# BEESP_CODE_io.net
KiCad netlist of a schematic drawn in Altium Designer
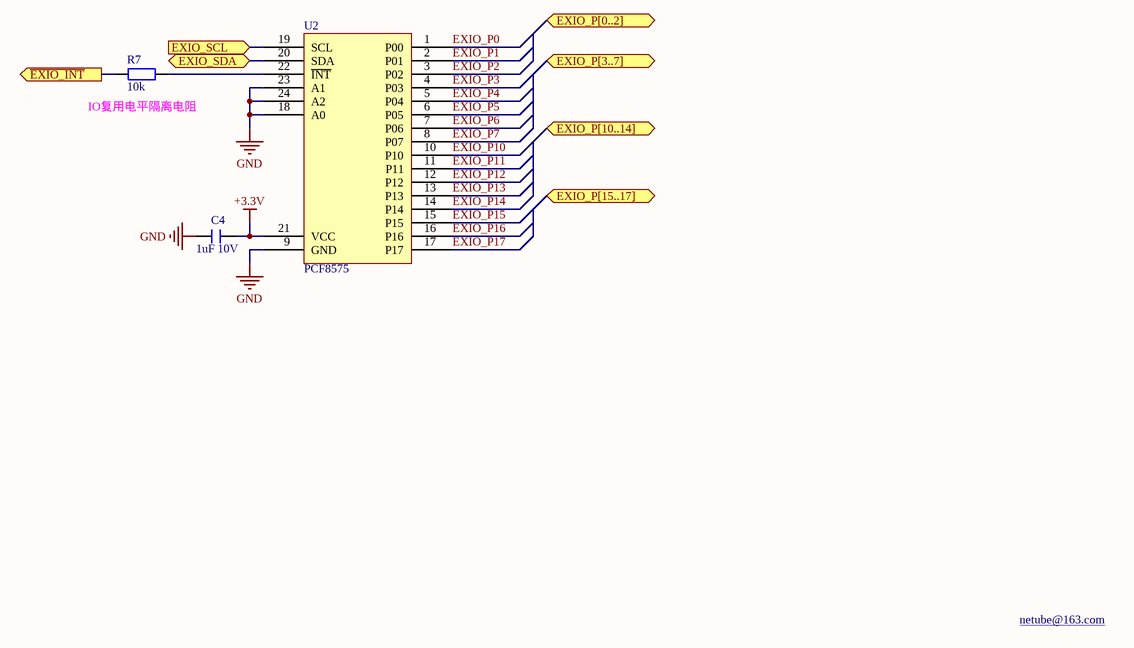
[diagram p0: BEESP_CODE_io.SchDoc]

(export (version "E")
  (design (tool "Eeschema 10.0.6"))
  (components
    (comp (ref "C4")
      (value "1uF 10V")
      (footprint "C 0402_L")
      (description "贴片电容")
      (libsource (lib "0.1 - 电阻-电容-电感") (part "C"))
    )
    (comp (ref "R7")
      (value "10k")
      (footprint "R 0402_L")
      (description "贴片电阻")
      (libsource (lib "0.1 - 电阻-电容-电感") (part "R"))
    )
    (comp (ref "U2") (value "PCF8575") (footprint "QFN24 4x4_N") (libsource (lib "IO拓展") (part "PCF8575")))
  )
  (nets
    (net (code "1") (name "+3.3V") (class "Default")
      (node (ref "C4") (pin "2") (pinfunction "2_2") (pintype "passive"))
      (node (ref "U2") (pin "21") (pinfunction "VCC_21") (pintype "passive"))
    )
    (net (code "2") (name "/EXIO_P0") (class "Default")
      (node (ref "U2") (pin "1") (pinfunction "P00_1") (pintype "passive"))
    )
    (net (code "3") (name "/EXIO_P1") (class "Default")
      (node (ref "U2") (pin "2") (pinfunction "P01_2") (pintype "passive"))
    )
    (net (code "4") (name "/EXIO_P2") (class "Default")
      (node (ref "U2") (pin "3") (pinfunction "P02_3") (pintype "passive"))
    )
    (net (code "5") (name "/EXIO_P3") (class "Default")
      (node (ref "U2") (pin "4") (pinfunction "P03_4") (pintype "passive"))
    )
    (net (code "6") (name "/EXIO_P4") (class "Default")
      (node (ref "U2") (pin "5") (pinfunction "P04_5") (pintype "passive"))
    )
    (net (code "7") (name "/EXIO_P5") (class "Default")
      (node (ref "U2") (pin "6") (pinfunction "P05_6") (pintype "passive"))
    )
    (net (code "8") (name "/EXIO_P6") (class "Default")
      (node (ref "U2") (pin "7") (pinfunction "P06_7") (pintype "passive"))
    )
    (net (code "9") (name "/EXIO_P7") (class "Default")
      (node (ref "U2") (pin "8") (pinfunction "P07_8") (pintype "passive"))
    )
    (net (code "10") (name "/EXIO_P10") (class "Default")
      (node (ref "U2") (pin "10") (pinfunction "P10_10") (pintype "passive"))
    )
    (net (code "11") (name "/EXIO_P11") (class "Default")
      (node (ref "U2") (pin "11") (pinfunction "P11_11") (pintype "passive"))
    )
    (net (code "12") (name "/EXIO_P12") (class "Default")
      (node (ref "U2") (pin "12") (pinfunction "P12_12") (pintype "passive"))
    )
    (net (code "13") (name "/EXIO_P13") (class "Default")
      (node (ref "U2") (pin "13") (pinfunction "P13_13") (pintype "passive"))
    )
    (net (code "14") (name "/EXIO_P14") (class "Default")
      (node (ref "U2") (pin "14") (pinfunction "P14_14") (pintype "passive"))
    )
    (net (code "15") (name "/EXIO_P15") (class "Default")
      (node (ref "U2") (pin "15") (pinfunction "P15_15") (pintype "passive"))
    )
    (net (code "16") (name "/EXIO_P16") (class "Default")
      (node (ref "U2") (pin "16") (pinfunction "P16_16") (pintype "passive"))
    )
    (net (code "17") (name "/EXIO_P17") (class "Default")
      (node (ref "U2") (pin "17") (pinfunction "P17_17") (pintype "passive"))
    )
    (net (code "22") (name "/EXIO_SCL") (class "Default")
      (node (ref "U2") (pin "19") (pinfunction "SCL_19") (pintype "passive"))
    )
    (net (code "23") (name "/EXIO_SDA") (class "Default")
      (node (ref "U2") (pin "20") (pinfunction "SDA_20") (pintype "passive"))
    )
    (net (code "24") (name "/~{EXIO_INT}") (class "Default")
      (node (ref "R7") (pin "2") (pinfunction "2_2") (pintype "passive"))
    )
    (net (code "25") (name "GND") (class "Default")
      (node (ref "C4") (pin "1") (pinfunction "1_1") (pintype "passive"))
      (node (ref "U2") (pin "18") (pinfunction "A0_18") (pintype "passive"))
      (node (ref "U2") (pin "23") (pinfunction "A1_23") (pintype "passive"))
      (node (ref "U2") (pin "24") (pinfunction "A2_24") (pintype "passive"))
      (node (ref "U2") (pin "9") (pinfunction "GND_9") (pintype "passive"))
    )
    (net (code "26") (name "Net-(U2-~{INT})") (class "Default")
      (node (ref "R7") (pin "1") (pinfunction "1_1") (pintype "passive"))
      (node (ref "U2") (pin "22") (pinfunction "~{INT}_22") (pintype "passive"))
    )
  )
)
